# Sheet1.net
KiCad netlist of a schematic drawn in Altium Designer
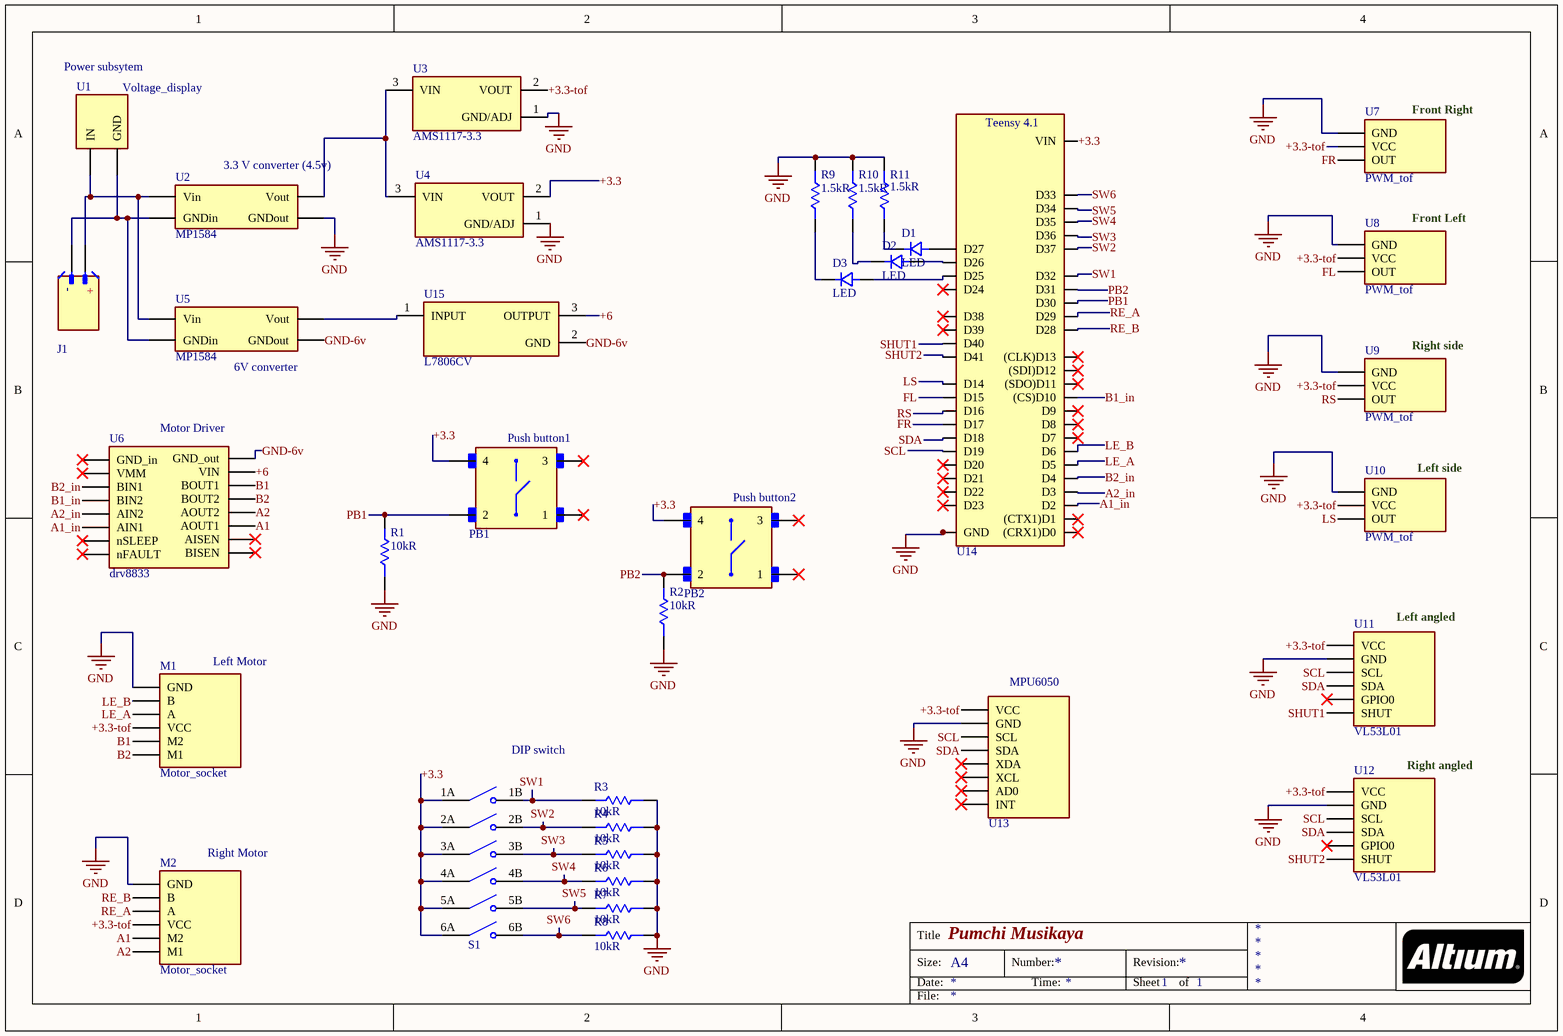
[diagram p0: Sheet1.SchDoc]

(export (version "E")
  (design (tool "Eeschema 10.0.6"))
  (components
    (comp (ref "D1")
      (value "LED")
      (footprint "150080RS75000")
      (description "Single Color LED, Red, Water Clear, 1.4mm")
      (fields
        (field (name "MANUFACTURER") "Wurth Electronics")
        (field (name "MANUFACTURER PART NUMBER") "150080RS75000")
      )
      (libsource (lib "EDP_integrated_library") (part "150080RS75000"))
    )
    (comp (ref "D2")
      (value "LED")
      (footprint "150080RS75000")
      (description "Single Color LED, Red, Water Clear, 1.4mm")
      (fields
        (field (name "MANUFACTURER") "Wurth Electronics")
        (field (name "MANUFACTURER PART NUMBER") "150080RS75000")
      )
      (libsource (lib "EDP_integrated_library") (part "150080RS75000"))
    )
    (comp (ref "D3")
      (value "LED")
      (footprint "150080RS75000")
      (description "Single Color LED, Red, Water Clear, 1.4mm")
      (fields
        (field (name "MANUFACTURER") "Wurth Electronics")
        (field (name "MANUFACTURER PART NUMBER") "150080RS75000")
      )
      (libsource (lib "EDP_integrated_library") (part "150080RS75000"))
    )
    (comp (ref "J1")
      (value "Power_jack")
      (footprint "Power_jack")
      (libsource (lib "Integrated_Library_pumchi_musikaya") (part "Power_jack"))
    )
    (comp (ref "M1")
      (value "Motor_socket")
      (footprint "Motor_socket")
      (libsource (lib "Integrated_Library_pumchi_musikaya") (part "Motor_socket"))
    )
    (comp (ref "M2")
      (value "Motor_socket")
      (footprint "Motor_socket")
      (libsource (lib "Integrated_Library_pumchi_musikaya") (part "Motor_socket"))
    )
    (comp (ref "PB1")
      (value "Push_button")
      (footprint "Push_button")
      (libsource (lib "Integrated_Library_pumchi_musikaya") (part "Push_button"))
    )
    (comp (ref "PB2")
      (value "Push_button")
      (footprint "Push_button")
      (libsource (lib "Integrated_Library_pumchi_musikaya") (part "Push_button"))
    )
    (comp (ref "R1")
      (value "10kR")
      (footprint "RC0805JR-0710KL")
      (fields
        (field (name "MANUFACTURER") "Yageo")
        (field (name "MANUFACTURER PART NUMBER") "RC0805JR-0710KL")
        (field (name "TOLERANCE") "5%")
      )
      (libsource (lib "EDP_integrated_library") (part "RC0805JR-0710KL"))
    )
    (comp (ref "R2")
      (value "10kR")
      (footprint "RC0805JR-0710KL")
      (fields
        (field (name "MANUFACTURER") "Yageo")
        (field (name "MANUFACTURER PART NUMBER") "RC0805JR-0710KL")
        (field (name "TOLERANCE") "5%")
      )
      (libsource (lib "EDP_integrated_library") (part "RC0805JR-0710KL"))
    )
    (comp (ref "R3")
      (value "10kR")
      (footprint "RC0805JR-0710KL")
      (fields
        (field (name "MANUFACTURER") "Yageo")
        (field (name "MANUFACTURER PART NUMBER") "RC0805JR-0710KL")
        (field (name "TOLERANCE") "5%")
      )
      (libsource (lib "EDP_integrated_library") (part "RC0805JR-0710KL"))
    )
    (comp (ref "R4")
      (value "10kR")
      (footprint "RC0805JR-0710KL")
      (fields
        (field (name "MANUFACTURER") "Yageo")
        (field (name "MANUFACTURER PART NUMBER") "RC0805JR-0710KL")
        (field (name "TOLERANCE") "5%")
      )
      (libsource (lib "EDP_integrated_library") (part "RC0805JR-0710KL"))
    )
    (comp (ref "R5")
      (value "10kR")
      (footprint "RC0805JR-0710KL")
      (fields
        (field (name "MANUFACTURER") "Yageo")
        (field (name "MANUFACTURER PART NUMBER") "RC0805JR-0710KL")
        (field (name "TOLERANCE") "5%")
      )
      (libsource (lib "EDP_integrated_library") (part "RC0805JR-0710KL"))
    )
    (comp (ref "R6")
      (value "10kR")
      (footprint "RC0805JR-0710KL")
      (fields
        (field (name "MANUFACTURER") "Yageo")
        (field (name "MANUFACTURER PART NUMBER") "RC0805JR-0710KL")
        (field (name "TOLERANCE") "5%")
      )
      (libsource (lib "EDP_integrated_library") (part "RC0805JR-0710KL"))
    )
    (comp (ref "R7")
      (value "10kR")
      (footprint "RC0805JR-0710KL")
      (fields
        (field (name "MANUFACTURER") "Yageo")
        (field (name "MANUFACTURER PART NUMBER") "RC0805JR-0710KL")
        (field (name "TOLERANCE") "5%")
      )
      (libsource (lib "EDP_integrated_library") (part "RC0805JR-0710KL"))
    )
    (comp (ref "R8")
      (value "10kR")
      (footprint "RC0805JR-0710KL")
      (fields
        (field (name "MANUFACTURER") "Yageo")
        (field (name "MANUFACTURER PART NUMBER") "RC0805JR-0710KL")
        (field (name "TOLERANCE") "5%")
      )
      (libsource (lib "EDP_integrated_library") (part "RC0805JR-0710KL"))
    )
    (comp (ref "R9")
      (value "1.5kR")
      (footprint "RC0805FR-071K5L")
      (fields
        (field (name "MANUFACTURER") "Yageo")
        (field (name "MANUFACTURER PART NUMBER") "RC0805FR-071K5L")
        (field (name "TOLERANCE") "1%")
      )
      (libsource (lib "EDP_integrated_library") (part "RC0805FR-071K5L"))
    )
    (comp (ref "R10")
      (value "1.5kR")
      (footprint "RC0805FR-071K5L")
      (fields
        (field (name "MANUFACTURER") "Yageo")
        (field (name "MANUFACTURER PART NUMBER") "RC0805FR-071K5L")
        (field (name "TOLERANCE") "1%")
      )
      (libsource (lib "EDP_integrated_library") (part "RC0805FR-071K5L"))
    )
    (comp (ref "R11")
      (value "1.5kR")
      (footprint "RC0805FR-071K5L")
      (fields
        (field (name "MANUFACTURER") "Yageo")
        (field (name "MANUFACTURER PART NUMBER") "RC0805FR-071K5L")
        (field (name "TOLERANCE") "1%")
      )
      (libsource (lib "EDP_integrated_library") (part "RC0805FR-071K5L"))
    )
    (comp (ref "S1")
      (value "DIP_switch")
      (footprint "DIP_switch")
      (libsource (lib "Integrated_Library_pumchi_musikaya") (part "DIP_switch"))
    )
    (comp (ref "U1")
      (value "Voltage_display")
      (footprint "Voltage_display")
      (libsource (lib "Integrated_Library_pumchi_musikaya") (part "Voltage_display"))
    )
    (comp (ref "U2")
      (value "MP1584")
      (footprint "MP1584")
      (libsource (lib "Integrated_Library_pumchi_musikaya") (part "MP1584"))
    )
    (comp (ref "U3")
      (value "AMS1117-3.3")
      (footprint "AMS1117-3.3")
      (libsource (lib "Integrated_Library_pumchi_musikaya") (part "AMS1117-3.3"))
    )
    (comp (ref "U4")
      (value "AMS1117-3.3")
      (footprint "AMS1117-3.3")
      (libsource (lib "Integrated_Library_pumchi_musikaya") (part "AMS1117-3.3"))
    )
    (comp (ref "U5")
      (value "MP1584")
      (footprint "MP1584")
      (libsource (lib "Integrated_Library_pumchi_musikaya") (part "MP1584"))
    )
    (comp (ref "U6")
      (value "drv8833")
      (footprint "drv8833")
      (libsource (lib "Integrated_Library_pumchi_musikaya") (part "drv8833"))
    )
    (comp (ref "U7")
      (value "PWM_tof")
      (footprint "P_tof")
      (libsource (lib "Integrated_Library_pumchi_musikaya") (part "P_tof"))
    )
    (comp (ref "U8")
      (value "PWM_tof")
      (footprint "P_tof")
      (libsource (lib "Integrated_Library_pumchi_musikaya") (part "P_tof"))
    )
    (comp (ref "U9")
      (value "PWM_tof")
      (footprint "P_tof")
      (libsource (lib "Integrated_Library_pumchi_musikaya") (part "P_tof"))
    )
    (comp (ref "U10")
      (value "PWM_tof")
      (footprint "P_tof")
      (libsource (lib "Integrated_Library_pumchi_musikaya") (part "P_tof"))
    )
    (comp (ref "U11")
      (value "VL53L01")
      (footprint "VL530L01")
      (libsource (lib "Integrated_Library_pumchi_musikaya") (part "VL53L01"))
    )
    (comp (ref "U12")
      (value "VL53L01")
      (footprint "VL530L01")
      (libsource (lib "Integrated_Library_pumchi_musikaya") (part "VL53L01"))
    )
    (comp (ref "U13")
      (value "MPU6050")
      (footprint "MPU6050")
      (libsource (lib "Integrated_Library_pumchi_musikaya") (part "MPU6050"))
    )
    (comp (ref "U14")
      (value "teensy4.1")
      (footprint "teensy4.1")
      (libsource (lib "Integrated_Library_pumchi_musikaya") (part "teensy4.1"))
    )
    (comp (ref "U15")
      (value "L7806CV")
      (footprint "L7806CV")
      (libsource (lib "Integrated_Library_pumchi_musikaya") (part "L7806CV"))
    )
  )
  (nets
    (net (code "1") (name "/+3.3") (class "Default")
      (node (ref "PB1") (pin "4") (pinfunction "4_4") (pintype "passive"))
      (node (ref "PB2") (pin "4") (pinfunction "4_4") (pintype "passive"))
      (node (ref "S1") (pin "1A") (pinfunction "COM1_1A") (pintype "passive"))
      (node (ref "S1") (pin "2A") (pinfunction "COM2_2A") (pintype "passive"))
      (node (ref "S1") (pin "3A") (pinfunction "COM3_3A") (pintype "passive"))
      (node (ref "S1") (pin "4A") (pinfunction "COM4_4A") (pintype "passive"))
      (node (ref "S1") (pin "5A") (pinfunction "COM5_5A") (pintype "passive"))
      (node (ref "S1") (pin "6A") (pinfunction "COM6_6A") (pintype "passive"))
      (node (ref "U14") (pin "VIN") (pinfunction "VIN_VIN") (pintype "power_in"))
      (node (ref "U4") (pin "2") (pinfunction "VOUT_2") (pintype "power_in"))
    )
    (net (code "2") (name "/+3.3-tof") (class "Default")
      (node (ref "M1") (pin "VCC") (pinfunction "VCC_VCC") (pintype "passive"))
      (node (ref "M2") (pin "VCC") (pinfunction "VCC_VCC") (pintype "passive"))
      (node (ref "U10") (pin "02") (pinfunction "VCC_02") (pintype "passive"))
      (node (ref "U11") (pin "01") (pinfunction "VCC_01") (pintype "passive"))
      (node (ref "U12") (pin "01") (pinfunction "VCC_01") (pintype "passive"))
      (node (ref "U13") (pin "01") (pinfunction "VCC_01") (pintype "passive"))
      (node (ref "U3") (pin "2") (pinfunction "VOUT_2") (pintype "power_in"))
      (node (ref "U7") (pin "02") (pinfunction "VCC_02") (pintype "passive"))
      (node (ref "U8") (pin "02") (pinfunction "VCC_02") (pintype "passive"))
      (node (ref "U9") (pin "02") (pinfunction "VCC_02") (pintype "passive"))
    )
    (net (code "3") (name "/+6") (class "Default")
      (node (ref "U15") (pin "3") (pinfunction "OUTPUT_3") (pintype "power_in"))
      (node (ref "U6") (pin "VIN") (pinfunction "VIN_VIN") (pintype "passive"))
    )
    (net (code "4") (name "/A1") (class "Default")
      (node (ref "M2") (pin "M2") (pinfunction "M2_M2") (pintype "passive"))
      (node (ref "U6") (pin "AOUT1") (pinfunction "AOUT1_AOUT1") (pintype "passive"))
    )
    (net (code "5") (name "/A1_in") (class "Default")
      (node (ref "U14") (pin "D2") (pinfunction "D2_D2") (pintype "bidirectional"))
      (node (ref "U6") (pin "AIN1") (pinfunction "AIN1_AIN1") (pintype "passive"))
    )
    (net (code "6") (name "/A2") (class "Default")
      (node (ref "M2") (pin "M1") (pinfunction "M1_M1") (pintype "passive"))
      (node (ref "U6") (pin "AOUT2") (pinfunction "AOUT2_AOUT2") (pintype "passive"))
    )
    (net (code "7") (name "/A2_in") (class "Default")
      (node (ref "U14") (pin "D3") (pinfunction "D3_D3") (pintype "bidirectional"))
      (node (ref "U6") (pin "AIN2") (pinfunction "AIN2_AIN2") (pintype "passive"))
    )
    (net (code "8") (name "/B1") (class "Default")
      (node (ref "M1") (pin "M2") (pinfunction "M2_M2") (pintype "passive"))
      (node (ref "U6") (pin "BOUT1") (pinfunction "BOUT1_BOUT1") (pintype "passive"))
    )
    (net (code "9") (name "/B1_in") (class "Default")
      (node (ref "U14") (pin "D10") (pinfunction "(CS)D10_D10") (pintype "bidirectional"))
      (node (ref "U6") (pin "BIN2") (pinfunction "BIN2_BIN2") (pintype "passive"))
    )
    (net (code "10") (name "/B2") (class "Default")
      (node (ref "M1") (pin "M1") (pinfunction "M1_M1") (pintype "passive"))
      (node (ref "U6") (pin "BOUT2") (pinfunction "BOUT2_BOUT2") (pintype "passive"))
    )
    (net (code "11") (name "/B2_in") (class "Default")
      (node (ref "U14") (pin "D4") (pinfunction "D4_D4") (pintype "bidirectional"))
      (node (ref "U6") (pin "BIN1") (pinfunction "BIN1_BIN1") (pintype "passive"))
    )
    (net (code "12") (name "/FL") (class "Default")
      (node (ref "U14") (pin "D15") (pinfunction "D15_D15") (pintype "bidirectional"))
      (node (ref "U8") (pin "03") (pinfunction "OUT_03") (pintype "passive"))
    )
    (net (code "13") (name "/FR") (class "Default")
      (node (ref "U14") (pin "D17") (pinfunction "D17_D17") (pintype "bidirectional"))
      (node (ref "U7") (pin "03") (pinfunction "OUT_03") (pintype "passive"))
    )
    (net (code "14") (name "/GND-6v") (class "Default")
      (node (ref "U15") (pin "2") (pinfunction "GND_2") (pintype "power_in"))
      (node (ref "U5") (pin "GNDout") (pinfunction "GNDout_GNDout") (pintype "passive"))
      (node (ref "U6") (pin "GND_out") (pinfunction "GND_out_GND_out") (pintype "passive"))
    )
    (net (code "15") (name "/LE_A") (class "Default")
      (node (ref "M1") (pin "A") (pinfunction "A_A") (pintype "passive"))
      (node (ref "U14") (pin "D5") (pinfunction "D5_D5") (pintype "bidirectional"))
    )
    (net (code "16") (name "/LE_B") (class "Default")
      (node (ref "M1") (pin "B") (pinfunction "B_B") (pintype "passive"))
      (node (ref "U14") (pin "D6") (pinfunction "D6_D6") (pintype "bidirectional"))
    )
    (net (code "17") (name "/LS") (class "Default")
      (node (ref "U10") (pin "03") (pinfunction "OUT_03") (pintype "passive"))
      (node (ref "U14") (pin "D14") (pinfunction "D14_D14") (pintype "bidirectional"))
    )
    (net (code "18") (name "/PB1") (class "Default")
      (node (ref "PB1") (pin "2") (pinfunction "2_2") (pintype "passive"))
      (node (ref "R1") (pin "2") (pinfunction "2_2") (pintype "passive"))
      (node (ref "U14") (pin "D30") (pinfunction "D30_D30") (pintype "bidirectional"))
    )
    (net (code "19") (name "/PB2") (class "Default")
      (node (ref "PB2") (pin "2") (pinfunction "2_2") (pintype "passive"))
      (node (ref "R2") (pin "2") (pinfunction "2_2") (pintype "passive"))
      (node (ref "U14") (pin "D31") (pinfunction "D31_D31") (pintype "bidirectional"))
    )
    (net (code "20") (name "/RE_A") (class "Default")
      (node (ref "M2") (pin "A") (pinfunction "A_A") (pintype "passive"))
      (node (ref "U14") (pin "D29") (pinfunction "D29_D29") (pintype "bidirectional"))
    )
    (net (code "21") (name "/RE_B") (class "Default")
      (node (ref "M2") (pin "B") (pinfunction "B_B") (pintype "passive"))
      (node (ref "U14") (pin "D28") (pinfunction "D28_D28") (pintype "bidirectional"))
    )
    (net (code "22") (name "/RS") (class "Default")
      (node (ref "U14") (pin "D16") (pinfunction "D16_D16") (pintype "bidirectional"))
      (node (ref "U9") (pin "03") (pinfunction "OUT_03") (pintype "passive"))
    )
    (net (code "23") (name "/SCL") (class "Default")
      (node (ref "U11") (pin "03") (pinfunction "SCL_03") (pintype "passive"))
      (node (ref "U12") (pin "03") (pinfunction "SCL_03") (pintype "passive"))
      (node (ref "U13") (pin "03") (pinfunction "SCL_03") (pintype "passive"))
      (node (ref "U14") (pin "D19") (pinfunction "D19_D19") (pintype "bidirectional"))
    )
    (net (code "24") (name "/SDA") (class "Default")
      (node (ref "U11") (pin "04") (pinfunction "SDA_04") (pintype "passive"))
      (node (ref "U12") (pin "04") (pinfunction "SDA_04") (pintype "passive"))
      (node (ref "U13") (pin "04") (pinfunction "SDA_04") (pintype "passive"))
      (node (ref "U14") (pin "D18") (pinfunction "D18_D18") (pintype "bidirectional"))
    )
    (net (code "25") (name "/SHUT1") (class "Default")
      (node (ref "U11") (pin "06") (pinfunction "SHUT_06") (pintype "passive"))
      (node (ref "U14") (pin "D40") (pinfunction "D40_D40") (pintype "bidirectional"))
    )
    (net (code "26") (name "/SHUT2") (class "Default")
      (node (ref "U12") (pin "06") (pinfunction "SHUT_06") (pintype "passive"))
      (node (ref "U14") (pin "D41") (pinfunction "D41_D41") (pintype "bidirectional"))
    )
    (net (code "27") (name "/SW1") (class "Default")
      (node (ref "R3") (pin "2") (pinfunction "2_2") (pintype "passive"))
      (node (ref "S1") (pin "1B") (pinfunction "NO1_1B") (pintype "passive"))
      (node (ref "U14") (pin "D32") (pinfunction "D32_D32") (pintype "bidirectional"))
    )
    (net (code "28") (name "/SW2") (class "Default")
      (node (ref "R4") (pin "2") (pinfunction "2_2") (pintype "passive"))
      (node (ref "S1") (pin "2B") (pinfunction "NO2_2B") (pintype "passive"))
      (node (ref "U14") (pin "D37") (pinfunction "D37_D37") (pintype "bidirectional"))
    )
    (net (code "29") (name "/SW3") (class "Default")
      (node (ref "R5") (pin "2") (pinfunction "2_2") (pintype "passive"))
      (node (ref "S1") (pin "3B") (pinfunction "NO3_3B") (pintype "passive"))
      (node (ref "U14") (pin "D36") (pinfunction "D36_D36") (pintype "bidirectional"))
    )
    (net (code "30") (name "/SW4") (class "Default")
      (node (ref "R6") (pin "2") (pinfunction "2_2") (pintype "passive"))
      (node (ref "S1") (pin "4B") (pinfunction "NO4_4B") (pintype "passive"))
      (node (ref "U14") (pin "D35") (pinfunction "D35_D35") (pintype "bidirectional"))
    )
    (net (code "31") (name "/SW5") (class "Default")
      (node (ref "R7") (pin "2") (pinfunction "2_2") (pintype "passive"))
      (node (ref "S1") (pin "5B") (pinfunction "NO5_5B") (pintype "passive"))
      (node (ref "U14") (pin "D34") (pinfunction "D34_D34") (pintype "bidirectional"))
    )
    (net (code "32") (name "/SW6") (class "Default")
      (node (ref "R8") (pin "2") (pinfunction "2_2") (pintype "passive"))
      (node (ref "S1") (pin "6B") (pinfunction "NO6_6B") (pintype "passive"))
      (node (ref "U14") (pin "D33") (pinfunction "D33_D33") (pintype "bidirectional"))
    )
    (net (code "33") (name "GND") (class "Default")
      (node (ref "M1") (pin "GND") (pinfunction "GND_GND") (pintype "passive"))
      (node (ref "M2") (pin "GND") (pinfunction "GND_GND") (pintype "passive"))
      (node (ref "R1") (pin "1") (pinfunction "1_1") (pintype "passive"))
      (node (ref "R10") (pin "1") (pinfunction "1_1") (pintype "passive"))
      (node (ref "R11") (pin "1") (pinfunction "1_1") (pintype "passive"))
      (node (ref "R2") (pin "1") (pinfunction "1_1") (pintype "passive"))
      (node (ref "R3") (pin "1") (pinfunction "1_1") (pintype "passive"))
      (node (ref "R4") (pin "1") (pinfunction "1_1") (pintype "passive"))
      (node (ref "R5") (pin "1") (pinfunction "1_1") (pintype "passive"))
      (node (ref "R6") (pin "1") (pinfunction "1_1") (pintype "passive"))
      (node (ref "R7") (pin "1") (pinfunction "1_1") (pintype "passive"))
      (node (ref "R8") (pin "1") (pinfunction "1_1") (pintype "passive"))
      (node (ref "R9") (pin "1") (pinfunction "1_1") (pintype "passive"))
      (node (ref "U10") (pin "01") (pinfunction "GND_01") (pintype "passive"))
      (node (ref "U11") (pin "02") (pinfunction "GND_02") (pintype "passive"))
      (node (ref "U12") (pin "02") (pinfunction "GND_02") (pintype "passive"))
      (node (ref "U13") (pin "02") (pinfunction "GND_02") (pintype "passive"))
      (node (ref "U14") (pin "AGND/GND") (pinfunction "GND_AGND/GND") (pintype "bidirectional"))
      (node (ref "U14") (pin "GND") (pinfunction "GND_GND") (pintype "bidirectional"))
      (node (ref "U14") (pin "GND@2") (pinfunction "GND_GND@2") (pintype "bidirectional"))
      (node (ref "U2") (pin "GNDout") (pinfunction "GNDout_GNDout") (pintype "passive"))
      (node (ref "U3") (pin "1") (pinfunction "GND/ADJ_1") (pintype "power_in"))
      (node (ref "U4") (pin "1") (pinfunction "GND/ADJ_1") (pintype "power_in"))
      (node (ref "U7") (pin "01") (pinfunction "GND_01") (pintype "passive"))
      (node (ref "U8") (pin "01") (pinfunction "GND_01") (pintype "passive"))
      (node (ref "U9") (pin "01") (pinfunction "GND_01") (pintype "passive"))
    )
    (net (code "34") (name "Net-(D1-Pad1)") (class "Default")
      (node (ref "D1") (pin "1") (pinfunction "1_1") (pintype "passive"))
      (node (ref "U14") (pin "D27") (pinfunction "D27_D27") (pintype "bidirectional"))
    )
    (net (code "35") (name "Net-(D1-Pad2)") (class "Default")
      (node (ref "D1") (pin "2") (pinfunction "2_2") (pintype "passive"))
      (node (ref "R11") (pin "2") (pinfunction "2_2") (pintype "passive"))
    )
    (net (code "36") (name "Net-(D2-Pad1)") (class "Default")
      (node (ref "D2") (pin "1") (pinfunction "1_1") (pintype "passive"))
      (node (ref "U14") (pin "D26") (pinfunction "D26_D26") (pintype "bidirectional"))
    )
    (net (code "37") (name "Net-(D2-Pad2)") (class "Default")
      (node (ref "D2") (pin "2") (pinfunction "2_2") (pintype "passive"))
      (node (ref "R10") (pin "2") (pinfunction "2_2") (pintype "passive"))
    )
    (net (code "38") (name "Net-(D3-Pad1)") (class "Default")
      (node (ref "D3") (pin "1") (pinfunction "1_1") (pintype "passive"))
      (node (ref "U14") (pin "D25") (pinfunction "D25_D25") (pintype "bidirectional"))
    )
    (net (code "39") (name "Net-(D3-Pad2)") (class "Default")
      (node (ref "D3") (pin "2") (pinfunction "2_2") (pintype "passive"))
      (node (ref "R9") (pin "2") (pinfunction "2_2") (pintype "passive"))
    )
    (net (code "40") (name "Net-(J1-Pad1)") (class "Default")
      (node (ref "J1") (pin "1") (pinfunction "1_1") (pintype "passive"))
      (node (ref "U1") (pin "IN") (pinfunction "IN_IN") (pintype "power_in"))
      (node (ref "U2") (pin "Vin") (pinfunction "Vin_Vin") (pintype "passive"))
      (node (ref "U5") (pin "Vin") (pinfunction "Vin_Vin") (pintype "passive"))
    )
    (net (code "41") (name "Net-(J1-Pad2)") (class "Default")
      (node (ref "J1") (pin "2") (pinfunction "2_2") (pintype "passive"))
      (node (ref "U1") (pin "GND") (pinfunction "GND_GND") (pintype "power_in"))
      (node (ref "U2") (pin "GNDin") (pinfunction "GNDin_GNDin") (pintype "passive"))
      (node (ref "U5") (pin "GNDin") (pinfunction "GNDin_GNDin") (pintype "passive"))
    )
    (net (code "42") (name "Net-(U3-VIN)") (class "Default")
      (node (ref "U2") (pin "Vout") (pinfunction "Vout_Vout") (pintype "passive"))
      (node (ref "U3") (pin "3") (pinfunction "VIN_3") (pintype "power_in"))
      (node (ref "U4") (pin "3") (pinfunction "VIN_3") (pintype "power_in"))
    )
    (net (code "43") (name "Net-(U15-INPUT)") (class "Default")
      (node (ref "U15") (pin "1") (pinfunction "INPUT_1") (pintype "power_in"))
      (node (ref "U5") (pin "Vout") (pinfunction "Vout_Vout") (pintype "passive"))
    )
    (net (code "44") (name "unconnected-(PB1-Pad1)") (class "Default")
      (node (ref "PB1") (pin "1") (pinfunction "1_1") (pintype "passive+no_connect"))
    )
    (net (code "45") (name "unconnected-(PB1-Pad3)") (class "Default")
      (node (ref "PB1") (pin "3") (pinfunction "3_3") (pintype "passive+no_connect"))
    )
    (net (code "46") (name "unconnected-(PB2-Pad1)") (class "Default")
      (node (ref "PB2") (pin "1") (pinfunction "1_1") (pintype "passive+no_connect"))
    )
    (net (code "47") (name "unconnected-(PB2-Pad3)") (class "Default")
      (node (ref "PB2") (pin "3") (pinfunction "3_3") (pintype "passive+no_connect"))
    )
    (net (code "48") (name "unconnected-(U6-PadAISEN)") (class "Default")
      (node (ref "U6") (pin "AISEN") (pinfunction "AISEN_AISEN") (pintype "passive+no_connect"))
    )
    (net (code "49") (name "unconnected-(U6-PadBISEN)") (class "Default")
      (node (ref "U6") (pin "BISEN") (pinfunction "BISEN_BISEN") (pintype "passive+no_connect"))
    )
    (net (code "50") (name "unconnected-(U6-PadGND_in)") (class "Default")
      (node (ref "U6") (pin "GND_in") (pinfunction "GND_in_GND_in") (pintype "passive+no_connect"))
    )
    (net (code "51") (name "unconnected-(U6-PadVMM)") (class "Default")
      (node (ref "U6") (pin "VMM") (pinfunction "VMM_VMM") (pintype "passive+no_connect"))
    )
    (net (code "52") (name "unconnected-(U6-PadnFAULT)") (class "Default")
      (node (ref "U6") (pin "nFAULT") (pinfunction "nFAULT_nFAULT") (pintype "passive+no_connect"))
    )
    (net (code "53") (name "unconnected-(U6-PadnSLEEP)") (class "Default")
      (node (ref "U6") (pin "nSLEEP") (pinfunction "nSLEEP_nSLEEP") (pintype "passive+no_connect"))
    )
    (net (code "54") (name "unconnected-(U11-GPIO0-Pad05)") (class "Default")
      (node (ref "U11") (pin "05") (pinfunction "GPIO0_05") (pintype "passive+no_connect"))
    )
    (net (code "55") (name "unconnected-(U12-GPIO0-Pad05)") (class "Default")
      (node (ref "U12") (pin "05") (pinfunction "GPIO0_05") (pintype "passive+no_connect"))
    )
    (net (code "56") (name "unconnected-(U13-AD0-Pad07)") (class "Default")
      (node (ref "U13") (pin "07") (pinfunction "AD0_07") (pintype "passive+no_connect"))
    )
    (net (code "57") (name "unconnected-(U13-INT-Pad08)") (class "Default")
      (node (ref "U13") (pin "08") (pinfunction "INT_08") (pintype "passive+no_connect"))
    )
    (net (code "58") (name "unconnected-(U13-XCL-Pad06)") (class "Default")
      (node (ref "U13") (pin "06") (pinfunction "XCL_06") (pintype "passive+no_connect"))
    )
    (net (code "59") (name "unconnected-(U13-XDA-Pad05)") (class "Default")
      (node (ref "U13") (pin "05") (pinfunction "XDA_05") (pintype "passive+no_connect"))
    )
    (net (code "60") (name "unconnected-(U14-(CLK)D13-PadD13)") (class "Default")
      (node (ref "U14") (pin "D13") (pinfunction "(CLK)D13_D13") (pintype "bidirectional+no_connect"))
    )
    (net (code "61") (name "unconnected-(U14-(CRX1)D0-PadD0)") (class "Default")
      (node (ref "U14") (pin "D0") (pinfunction "(CRX1)D0_D0") (pintype "bidirectional+no_connect"))
    )
    (net (code "62") (name "unconnected-(U14-(CTX1)D1-PadD1)") (class "Default")
      (node (ref "U14") (pin "D1") (pinfunction "(CTX1)D1_D1") (pintype "bidirectional+no_connect"))
    )
    (net (code "63") (name "unconnected-(U14-(SDI)D12-PadD12)") (class "Default")
      (node (ref "U14") (pin "D12") (pinfunction "(SDI)D12_D12") (pintype "bidirectional+no_connect"))
    )
    (net (code "64") (name "unconnected-(U14-(SDO)D11-PadD11)") (class "Default")
      (node (ref "U14") (pin "D11") (pinfunction "(SDO)D11_D11") (pintype "bidirectional+no_connect"))
    )
    (net (code "65") (name "unconnected-(U14-PadD7)") (class "Default")
      (node (ref "U14") (pin "D7") (pinfunction "D7_D7") (pintype "bidirectional+no_connect"))
    )
    (net (code "66") (name "unconnected-(U14-PadD8)") (class "Default")
      (node (ref "U14") (pin "D8") (pinfunction "D8_D8") (pintype "bidirectional+no_connect"))
    )
    (net (code "67") (name "unconnected-(U14-PadD9)") (class "Default")
      (node (ref "U14") (pin "D9") (pinfunction "D9_D9") (pintype "bidirectional+no_connect"))
    )
    (net (code "68") (name "unconnected-(U14-PadD20)") (class "Default")
      (node (ref "U14") (pin "D20") (pinfunction "D20_D20") (pintype "bidirectional+no_connect"))
    )
    (net (code "69") (name "unconnected-(U14-PadD21)") (class "Default")
      (node (ref "U14") (pin "D21") (pinfunction "D21_D21") (pintype "bidirectional+no_connect"))
    )
    (net (code "70") (name "unconnected-(U14-PadD22)") (class "Default")
      (node (ref "U14") (pin "D22") (pinfunction "D22_D22") (pintype "bidirectional+no_connect"))
    )
    (net (code "71") (name "unconnected-(U14-PadD23)") (class "Default")
      (node (ref "U14") (pin "D23") (pinfunction "D23_D23") (pintype "bidirectional+no_connect"))
    )
    (net (code "72") (name "unconnected-(U14-PadD24)") (class "Default")
      (node (ref "U14") (pin "D24") (pinfunction "D24_D24") (pintype "bidirectional+no_connect"))
    )
    (net (code "73") (name "unconnected-(U14-PadD38)") (class "Default")
      (node (ref "U14") (pin "D38") (pinfunction "D38_D38") (pintype "bidirectional+no_connect"))
    )
    (net (code "74") (name "unconnected-(U14-PadD39)") (class "Default")
      (node (ref "U14") (pin "D39") (pinfunction "D39_D39") (pintype "bidirectional+no_connect"))
    )
  )
)
